# Lipmouse_Daughterboard_FSRextern.net
KiCad netlist of a schematic drawn in EAGLE
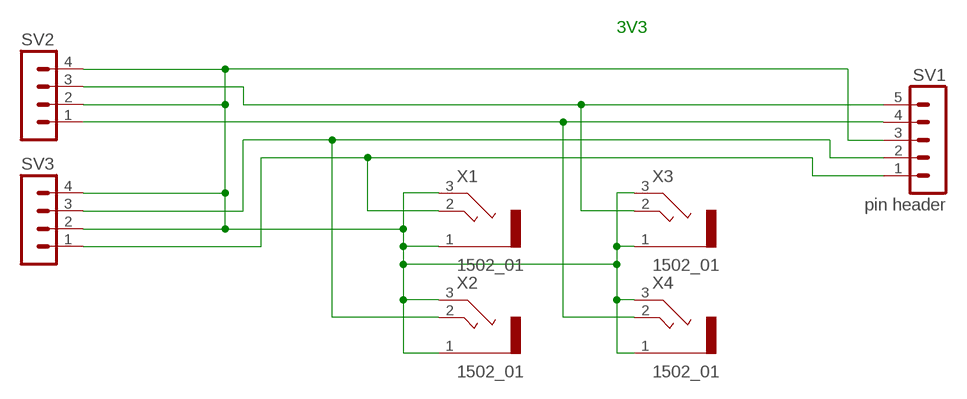
[diagram p0: schematic, sheet 1]

(export (version "E")
  (design (tool "Eeschema 10.0.6"))
  (components
    (comp (ref "SV1")
      (value "pin header")
      (footprint "eagle-import:MA05-1")
      (libsource (lib "eagle-import") (part "MA05-1"))
    )
    (comp (ref "SV2")
      (value "MA04-1")
      (footprint "eagle-import:MA04-1")
      (libsource (lib "eagle-import") (part "MA04-1"))
    )
    (comp (ref "SV3")
      (value "MA04-1")
      (footprint "eagle-import:MA04-1")
      (libsource (lib "eagle-import") (part "MA04-1"))
    )
    (comp (ref "X1")
      (value "1502_01")
      (footprint "eagle-import:1502_01")
      (libsource (lib "eagle-import") (part "1502_01"))
    )
    (comp (ref "X2")
      (value "1502_01")
      (footprint "eagle-import:1502_01")
      (libsource (lib "eagle-import") (part "1502_01"))
    )
    (comp (ref "X3")
      (value "1502_01")
      (footprint "eagle-import:1502_01")
      (libsource (lib "eagle-import") (part "1502_01"))
    )
    (comp (ref "X4")
      (value "1502_01")
      (footprint "eagle-import:1502_01")
      (libsource (lib "eagle-import") (part "1502_01"))
    )
  )
  (nets
    (net (code "1") (name "Net-(X1-2)") (class "Default")
      (node (ref "SV1") (pin "3") (pinfunction "3_3") (pintype "passive"))
      (node (ref "SV2") (pin "2") (pinfunction "2_2") (pintype "passive"))
      (node (ref "SV2") (pin "4") (pinfunction "4_4") (pintype "passive"))
      (node (ref "SV3") (pin "2") (pinfunction "2_2") (pintype "passive"))
      (node (ref "SV3") (pin "4") (pinfunction "4_4") (pintype "passive"))
      (node (ref "X1") (pin "1") (pinfunction "1_1") (pintype "passive"))
      (node (ref "X1") (pin "3") (pinfunction "2_3") (pintype "passive"))
      (node (ref "X2") (pin "1") (pinfunction "1_1") (pintype "passive"))
      (node (ref "X2") (pin "3") (pinfunction "2_3") (pintype "passive"))
      (node (ref "X3") (pin "1") (pinfunction "1_1") (pintype "passive"))
      (node (ref "X3") (pin "3") (pinfunction "2_3") (pintype "passive"))
      (node (ref "X4") (pin "1") (pinfunction "1_1") (pintype "passive"))
      (node (ref "X4") (pin "3") (pinfunction "2_3") (pintype "passive"))
    )
    (net (code "2") (name "Net-(X1-3)") (class "Default")
      (node (ref "SV1") (pin "1") (pinfunction "1_1") (pintype "passive"))
      (node (ref "SV3") (pin "1") (pinfunction "1_1") (pintype "passive"))
      (node (ref "X1") (pin "2") (pinfunction "3_2") (pintype "passive"))
    )
    (net (code "3") (name "Net-(X2-3)") (class "Default")
      (node (ref "SV1") (pin "2") (pinfunction "2_2") (pintype "passive"))
      (node (ref "SV3") (pin "3") (pinfunction "3_3") (pintype "passive"))
      (node (ref "X2") (pin "2") (pinfunction "3_2") (pintype "passive"))
    )
    (net (code "4") (name "Net-(X3-3)") (class "Default")
      (node (ref "SV1") (pin "5") (pinfunction "5_5") (pintype "passive"))
      (node (ref "SV2") (pin "3") (pinfunction "3_3") (pintype "passive"))
      (node (ref "X3") (pin "2") (pinfunction "3_2") (pintype "passive"))
    )
    (net (code "5") (name "Net-(X4-3)") (class "Default")
      (node (ref "SV1") (pin "4") (pinfunction "4_4") (pintype "passive"))
      (node (ref "SV2") (pin "1") (pinfunction "1_1") (pintype "passive"))
      (node (ref "X4") (pin "2") (pinfunction "3_2") (pintype "passive"))
    )
  )
)
